# LT4320_1.net
KiCad netlist of a schematic drawn in Altium Designer
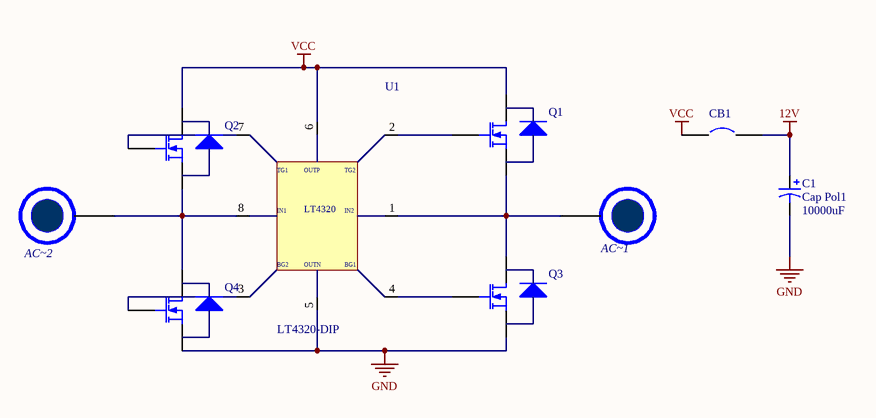
[diagram p0: LT4320_1.SchDoc]

(export (version "E")
  (design (tool "Eeschema 10.0.6"))
  (components
    (comp (ref "AC~1") (value "PIN") (footprint "PIN") (libsource (lib "常用元件库") (part "PIN")))
    (comp (ref "AC~2") (value "PIN") (footprint "PIN") (libsource (lib "常用元件库") (part "PIN")))
    (comp (ref "C1")
      (value "Cap Pol1")
      (footprint "RB7.6-15")
      (description "Polarized Capacitor (Radial)")
      (fields (field (name "ALTIUM_VALUE") "10000uF") (field (name "PUBLISHER") "Altium Limited"))
      (libsource (lib "Miscellaneous Devices") (part "Cap Pol1"))
    )
    (comp (ref "CB1")
      (value "Circuit Breaker")
      (footprint "SPST-2")
      (fields (field (name "PUBLISHER") "Altium Limited"))
      (libsource (lib "Miscellaneous Devices") (part "Circuit Breaker"))
    )
    (comp (ref "Q1")
      (value "MOSFET-N")
      (footprint "mos")
      (description "N-Channel MOSFET")
      (fields (field (name "PUBLISHER") "Altium Limited"))
      (libsource (lib "原理图") (part "MOSFET-N"))
    )
    (comp (ref "Q2")
      (value "MOSFET-N")
      (footprint "mos")
      (description "N-Channel MOSFET")
      (fields (field (name "PUBLISHER") "Altium Limited"))
      (libsource (lib "原理图") (part "MOSFET-N"))
    )
    (comp (ref "Q3")
      (value "MOSFET-N")
      (footprint "mos")
      (description "N-Channel MOSFET")
      (fields (field (name "PUBLISHER") "Altium Limited"))
      (libsource (lib "原理图") (part "MOSFET-N"))
    )
    (comp (ref "Q4")
      (value "MOSFET-N")
      (footprint "mos")
      (description "N-Channel MOSFET")
      (fields (field (name "PUBLISHER") "Altium Limited"))
      (libsource (lib "原理图") (part "MOSFET-N"))
    )
    (comp (ref "U1") (value "LT4320-DIP") (footprint "DIP-8") (libsource (lib "2号库") (part "LT4320-DIP")))
  )
  (nets
    (net (code "1") (name "12V") (class "Default")
      (node (ref "C1") (pin "1") (pinfunction "1_1") (pintype "passive"))
      (node (ref "CB1") (pin "2") (pinfunction "2_2") (pintype "passive"))
    )
    (net (code "2") (name "GND") (class "Default")
      (node (ref "C1") (pin "2") (pinfunction "2_2") (pintype "passive"))
      (node (ref "Q3") (pin "3") (pinfunction "S_3") (pintype "passive"))
      (node (ref "Q4") (pin "3") (pinfunction "S_3") (pintype "passive"))
      (node (ref "U1") (pin "5") (pinfunction "5_5") (pintype "passive"))
    )
    (net (code "3") (name "Net-(AC~1-PIN)") (class "Default")
      (node (ref "AC~1") (pin "1") (pinfunction "PIN_1") (pintype "passive"))
      (node (ref "Q1") (pin "3") (pinfunction "S_3") (pintype "passive"))
      (node (ref "Q3") (pin "2") (pinfunction "D_2") (pintype "passive"))
      (node (ref "U1") (pin "1") (pinfunction "1_1") (pintype "passive"))
    )
    (net (code "4") (name "Net-(AC~2-PIN)") (class "Default")
      (node (ref "AC~2") (pin "1") (pinfunction "PIN_1") (pintype "passive"))
      (node (ref "Q2") (pin "3") (pinfunction "S_3") (pintype "passive"))
      (node (ref "Q4") (pin "2") (pinfunction "D_2") (pintype "passive"))
      (node (ref "U1") (pin "8") (pinfunction "8_8") (pintype "passive"))
    )
    (net (code "5") (name "Net-(Q1-G)") (class "Default")
      (node (ref "Q1") (pin "1") (pinfunction "G_1") (pintype "passive"))
      (node (ref "U1") (pin "2") (pinfunction "2_2") (pintype "passive"))
    )
    (net (code "6") (name "Net-(Q2-G)") (class "Default")
      (node (ref "Q2") (pin "1") (pinfunction "G_1") (pintype "passive"))
      (node (ref "U1") (pin "7") (pinfunction "7_7") (pintype "passive"))
    )
    (net (code "7") (name "Net-(Q3-G)") (class "Default")
      (node (ref "Q3") (pin "1") (pinfunction "G_1") (pintype "passive"))
      (node (ref "U1") (pin "4") (pinfunction "4_4") (pintype "passive"))
    )
    (net (code "8") (name "Net-(Q4-G)") (class "Default")
      (node (ref "Q4") (pin "1") (pinfunction "G_1") (pintype "passive"))
      (node (ref "U1") (pin "3") (pinfunction "3_3") (pintype "passive"))
    )
    (net (code "9") (name "VCC") (class "Default")
      (node (ref "CB1") (pin "1") (pinfunction "1_1") (pintype "passive"))
      (node (ref "Q1") (pin "2") (pinfunction "D_2") (pintype "passive"))
      (node (ref "Q2") (pin "2") (pinfunction "D_2") (pintype "passive"))
      (node (ref "U1") (pin "6") (pinfunction "6_6") (pintype "passive"))
    )
  )
)
